# V1_0.net
KiCad netlist of a schematic drawn in EAGLE
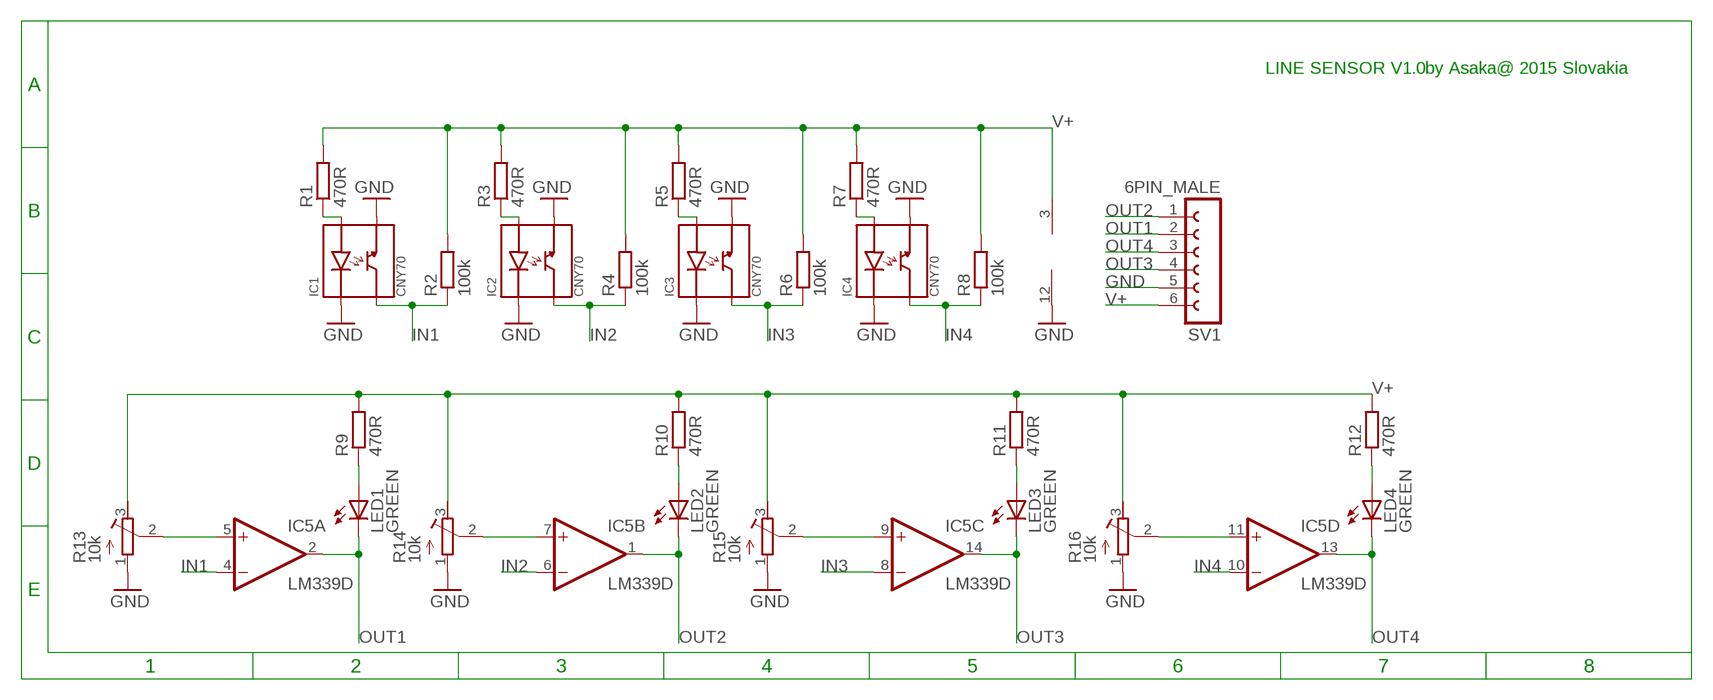
[diagram p0: schematic, sheet 1]

(export (version "E")
  (design (tool "Eeschema 10.0.6"))
  (components
    (comp (ref "IC1")
      (value "CNY70")
      (footprint "eagle-import:CNY70")
      (libsource (lib "eagle-import") (part "CNY70"))
    )
    (comp (ref "IC2")
      (value "CNY70")
      (footprint "eagle-import:CNY70")
      (libsource (lib "eagle-import") (part "CNY70"))
    )
    (comp (ref "IC3")
      (value "CNY70")
      (footprint "eagle-import:CNY70")
      (libsource (lib "eagle-import") (part "CNY70"))
    )
    (comp (ref "IC4")
      (value "CNY70")
      (footprint "eagle-import:CNY70")
      (libsource (lib "eagle-import") (part "CNY70"))
    )
    (comp (ref "IC5")
      (value "LM339D")
      (footprint "eagle-import:SO14")
      (libsource (lib "eagle-import") (part "LM339D"))
    )
    (comp (ref "LED1")
      (value "GREEN")
      (footprint "eagle-import:CHIP-LED0805")
      (libsource (lib "eagle-import") (part "LEDCHIP-LED0805"))
    )
    (comp (ref "LED2")
      (value "GREEN")
      (footprint "eagle-import:CHIP-LED0805")
      (libsource (lib "eagle-import") (part "LEDCHIP-LED0805"))
    )
    (comp (ref "LED3")
      (value "GREEN")
      (footprint "eagle-import:CHIP-LED0805")
      (libsource (lib "eagle-import") (part "LEDCHIP-LED0805"))
    )
    (comp (ref "LED4")
      (value "GREEN")
      (footprint "eagle-import:CHIP-LED0805")
      (libsource (lib "eagle-import") (part "LEDCHIP-LED0805"))
    )
    (comp (ref "R1")
      (value "470R")
      (footprint "eagle-import:M0805")
      (libsource (lib "eagle-import") (part "R-EU_M0805"))
    )
    (comp (ref "R2")
      (value "100k")
      (footprint "eagle-import:M0805")
      (libsource (lib "eagle-import") (part "R-EU_M0805"))
    )
    (comp (ref "R3")
      (value "470R")
      (footprint "eagle-import:M0805")
      (libsource (lib "eagle-import") (part "R-EU_M0805"))
    )
    (comp (ref "R4")
      (value "100k")
      (footprint "eagle-import:M0805")
      (libsource (lib "eagle-import") (part "R-EU_M0805"))
    )
    (comp (ref "R5")
      (value "470R")
      (footprint "eagle-import:M0805")
      (libsource (lib "eagle-import") (part "R-EU_M0805"))
    )
    (comp (ref "R6")
      (value "100k")
      (footprint "eagle-import:M0805")
      (libsource (lib "eagle-import") (part "R-EU_M0805"))
    )
    (comp (ref "R7")
      (value "470R")
      (footprint "eagle-import:M0805")
      (libsource (lib "eagle-import") (part "R-EU_M0805"))
    )
    (comp (ref "R8")
      (value "100k")
      (footprint "eagle-import:M0805")
      (libsource (lib "eagle-import") (part "R-EU_M0805"))
    )
    (comp (ref "R9")
      (value "470R")
      (footprint "eagle-import:M0805")
      (libsource (lib "eagle-import") (part "R-EU_M0805"))
    )
    (comp (ref "R10")
      (value "470R")
      (footprint "eagle-import:M0805")
      (libsource (lib "eagle-import") (part "R-EU_M0805"))
    )
    (comp (ref "R11")
      (value "470R")
      (footprint "eagle-import:M0805")
      (libsource (lib "eagle-import") (part "R-EU_M0805"))
    )
    (comp (ref "R12")
      (value "470R")
      (footprint "eagle-import:M0805")
      (libsource (lib "eagle-import") (part "R-EU_M0805"))
    )
    (comp (ref "R13")
      (value "10k")
      (footprint "eagle-import:RTRIM3202")
      (libsource (lib "eagle-import") (part "R-TRIMM3202"))
    )
    (comp (ref "R14")
      (value "10k")
      (footprint "eagle-import:RTRIM3202")
      (libsource (lib "eagle-import") (part "R-TRIMM3202"))
    )
    (comp (ref "R15")
      (value "10k")
      (footprint "eagle-import:RTRIM3202")
      (libsource (lib "eagle-import") (part "R-TRIMM3202"))
    )
    (comp (ref "R16")
      (value "10k")
      (footprint "eagle-import:RTRIM3202")
      (libsource (lib "eagle-import") (part "R-TRIMM3202"))
    )
    (comp (ref "SV1")
      (value "6PIN_MALE")
      (footprint "eagle-import:FE06")
      (libsource (lib "eagle-import") (part "FE06-1"))
    )
  )
  (nets
    (net (code "1") (name "/IN1") (class "Default")
      (node (ref "IC1") (pin "DC") (pinfunction "DC_DC") (pintype "bidirectional"))
      (node (ref "IC5") (pin "4") (pinfunction "-IN_4") (pintype "input"))
      (node (ref "R2") (pin "1") (pinfunction "1_1") (pintype "passive"))
    )
    (net (code "2") (name "/IN2") (class "Default")
      (node (ref "IC2") (pin "DC") (pinfunction "DC_DC") (pintype "bidirectional"))
      (node (ref "IC5") (pin "6") (pinfunction "-IN_6") (pintype "input"))
      (node (ref "R4") (pin "1") (pinfunction "1_1") (pintype "passive"))
    )
    (net (code "3") (name "/IN3") (class "Default")
      (node (ref "IC3") (pin "DC") (pinfunction "DC_DC") (pintype "bidirectional"))
      (node (ref "IC5") (pin "8") (pinfunction "-IN_8") (pintype "input"))
      (node (ref "R6") (pin "1") (pinfunction "1_1") (pintype "passive"))
    )
    (net (code "4") (name "/IN4") (class "Default")
      (node (ref "IC4") (pin "DC") (pinfunction "DC_DC") (pintype "bidirectional"))
      (node (ref "IC5") (pin "10") (pinfunction "-IN_10") (pintype "input"))
      (node (ref "R8") (pin "1") (pinfunction "1_1") (pintype "passive"))
    )
    (net (code "5") (name "/OUT1") (class "Default")
      (node (ref "IC5") (pin "2") (pinfunction "OUT_2") (pintype "open_collector"))
      (node (ref "LED1") (pin "C") (pinfunction "C_C") (pintype "passive"))
      (node (ref "SV1") (pin "2") (pinfunction "2_2") (pintype "passive"))
    )
    (net (code "6") (name "/OUT2") (class "Default")
      (node (ref "IC5") (pin "1") (pinfunction "OUT_1") (pintype "open_collector"))
      (node (ref "LED2") (pin "C") (pinfunction "C_C") (pintype "passive"))
      (node (ref "SV1") (pin "1") (pinfunction "1_1") (pintype "passive"))
    )
    (net (code "7") (name "/OUT3") (class "Default")
      (node (ref "IC5") (pin "14") (pinfunction "OUT_14") (pintype "open_collector"))
      (node (ref "LED3") (pin "C") (pinfunction "C_C") (pintype "passive"))
      (node (ref "SV1") (pin "4") (pinfunction "4_4") (pintype "passive"))
    )
    (net (code "8") (name "/OUT4") (class "Default")
      (node (ref "IC5") (pin "13") (pinfunction "OUT_13") (pintype "open_collector"))
      (node (ref "LED4") (pin "C") (pinfunction "C_C") (pintype "passive"))
      (node (ref "SV1") (pin "3") (pinfunction "3_3") (pintype "passive"))
    )
    (net (code "9") (name "/V+") (class "Default")
      (node (ref "IC5") (pin "3") (pinfunction "V+_3") (pintype "power_in"))
      (node (ref "R1") (pin "2") (pinfunction "2_2") (pintype "passive"))
      (node (ref "R10") (pin "2") (pinfunction "2_2") (pintype "passive"))
      (node (ref "R11") (pin "2") (pinfunction "2_2") (pintype "passive"))
      (node (ref "R12") (pin "2") (pinfunction "2_2") (pintype "passive"))
      (node (ref "R13") (pin "3") (pinfunction "A_3") (pintype "passive"))
      (node (ref "R14") (pin "3") (pinfunction "A_3") (pintype "passive"))
      (node (ref "R15") (pin "3") (pinfunction "A_3") (pintype "passive"))
      (node (ref "R16") (pin "3") (pinfunction "A_3") (pintype "passive"))
      (node (ref "R2") (pin "2") (pinfunction "2_2") (pintype "passive"))
      (node (ref "R3") (pin "2") (pinfunction "2_2") (pintype "passive"))
      (node (ref "R4") (pin "2") (pinfunction "2_2") (pintype "passive"))
      (node (ref "R5") (pin "2") (pinfunction "2_2") (pintype "passive"))
      (node (ref "R6") (pin "2") (pinfunction "2_2") (pintype "passive"))
      (node (ref "R7") (pin "2") (pinfunction "2_2") (pintype "passive"))
      (node (ref "R8") (pin "2") (pinfunction "2_2") (pintype "passive"))
      (node (ref "R9") (pin "2") (pinfunction "2_2") (pintype "passive"))
      (node (ref "SV1") (pin "6") (pinfunction "6_6") (pintype "passive"))
    )
    (net (code "10") (name "GND") (class "Default")
      (node (ref "IC1") (pin "DE") (pinfunction "DE_DE") (pintype "bidirectional"))
      (node (ref "IC1") (pin "EK") (pinfunction "EK_EK") (pintype "bidirectional"))
      (node (ref "IC2") (pin "DE") (pinfunction "DE_DE") (pintype "bidirectional"))
      (node (ref "IC2") (pin "EK") (pinfunction "EK_EK") (pintype "bidirectional"))
      (node (ref "IC3") (pin "DE") (pinfunction "DE_DE") (pintype "bidirectional"))
      (node (ref "IC3") (pin "EK") (pinfunction "EK_EK") (pintype "bidirectional"))
      (node (ref "IC4") (pin "DE") (pinfunction "DE_DE") (pintype "bidirectional"))
      (node (ref "IC4") (pin "EK") (pinfunction "EK_EK") (pintype "bidirectional"))
      (node (ref "IC5") (pin "12") (pinfunction "GND_12") (pintype "power_in"))
      (node (ref "R13") (pin "1") (pinfunction "E_1") (pintype "passive"))
      (node (ref "R14") (pin "1") (pinfunction "E_1") (pintype "passive"))
      (node (ref "R15") (pin "1") (pinfunction "E_1") (pintype "passive"))
      (node (ref "R16") (pin "1") (pinfunction "E_1") (pintype "passive"))
      (node (ref "SV1") (pin "5") (pinfunction "5_5") (pintype "passive"))
    )
    (net (code "11") (name "Net-(IC1-PadEA)") (class "Default")
      (node (ref "IC1") (pin "EA") (pinfunction "EA_EA") (pintype "bidirectional"))
      (node (ref "R1") (pin "1") (pinfunction "1_1") (pintype "passive"))
    )
    (net (code "12") (name "Net-(IC2-PadEA)") (class "Default")
      (node (ref "IC2") (pin "EA") (pinfunction "EA_EA") (pintype "bidirectional"))
      (node (ref "R3") (pin "1") (pinfunction "1_1") (pintype "passive"))
    )
    (net (code "13") (name "Net-(IC3-PadEA)") (class "Default")
      (node (ref "IC3") (pin "EA") (pinfunction "EA_EA") (pintype "bidirectional"))
      (node (ref "R5") (pin "1") (pinfunction "1_1") (pintype "passive"))
    )
    (net (code "14") (name "Net-(IC4-PadEA)") (class "Default")
      (node (ref "IC4") (pin "EA") (pinfunction "EA_EA") (pintype "bidirectional"))
      (node (ref "R7") (pin "1") (pinfunction "1_1") (pintype "passive"))
    )
    (net (code "15") (name "Net-(IC5A-+IN)") (class "Default")
      (node (ref "IC5") (pin "5") (pinfunction "+IN_5") (pintype "input"))
      (node (ref "R13") (pin "2") (pinfunction "S_2") (pintype "passive"))
    )
    (net (code "16") (name "Net-(IC5B-+IN)") (class "Default")
      (node (ref "IC5") (pin "7") (pinfunction "+IN_7") (pintype "input"))
      (node (ref "R14") (pin "2") (pinfunction "S_2") (pintype "passive"))
    )
    (net (code "17") (name "Net-(IC5C-+IN)") (class "Default")
      (node (ref "IC5") (pin "9") (pinfunction "+IN_9") (pintype "input"))
      (node (ref "R15") (pin "2") (pinfunction "S_2") (pintype "passive"))
    )
    (net (code "18") (name "Net-(IC5D-+IN)") (class "Default")
      (node (ref "IC5") (pin "11") (pinfunction "+IN_11") (pintype "input"))
      (node (ref "R16") (pin "2") (pinfunction "S_2") (pintype "passive"))
    )
    (net (code "19") (name "Net-(LED1-PadA)") (class "Default")
      (node (ref "LED1") (pin "A") (pinfunction "A_A") (pintype "passive"))
      (node (ref "R9") (pin "1") (pinfunction "1_1") (pintype "passive"))
    )
    (net (code "20") (name "Net-(LED2-PadA)") (class "Default")
      (node (ref "LED2") (pin "A") (pinfunction "A_A") (pintype "passive"))
      (node (ref "R10") (pin "1") (pinfunction "1_1") (pintype "passive"))
    )
    (net (code "21") (name "Net-(LED3-PadA)") (class "Default")
      (node (ref "LED3") (pin "A") (pinfunction "A_A") (pintype "passive"))
      (node (ref "R11") (pin "1") (pinfunction "1_1") (pintype "passive"))
    )
    (net (code "22") (name "Net-(LED4-PadA)") (class "Default")
      (node (ref "LED4") (pin "A") (pinfunction "A_A") (pintype "passive"))
      (node (ref "R12") (pin "1") (pinfunction "1_1") (pintype "passive"))
    )
  )
)
